# TC264_2024-10-17.net
KiCad netlist of a schematic drawn in EasyEDA Pro
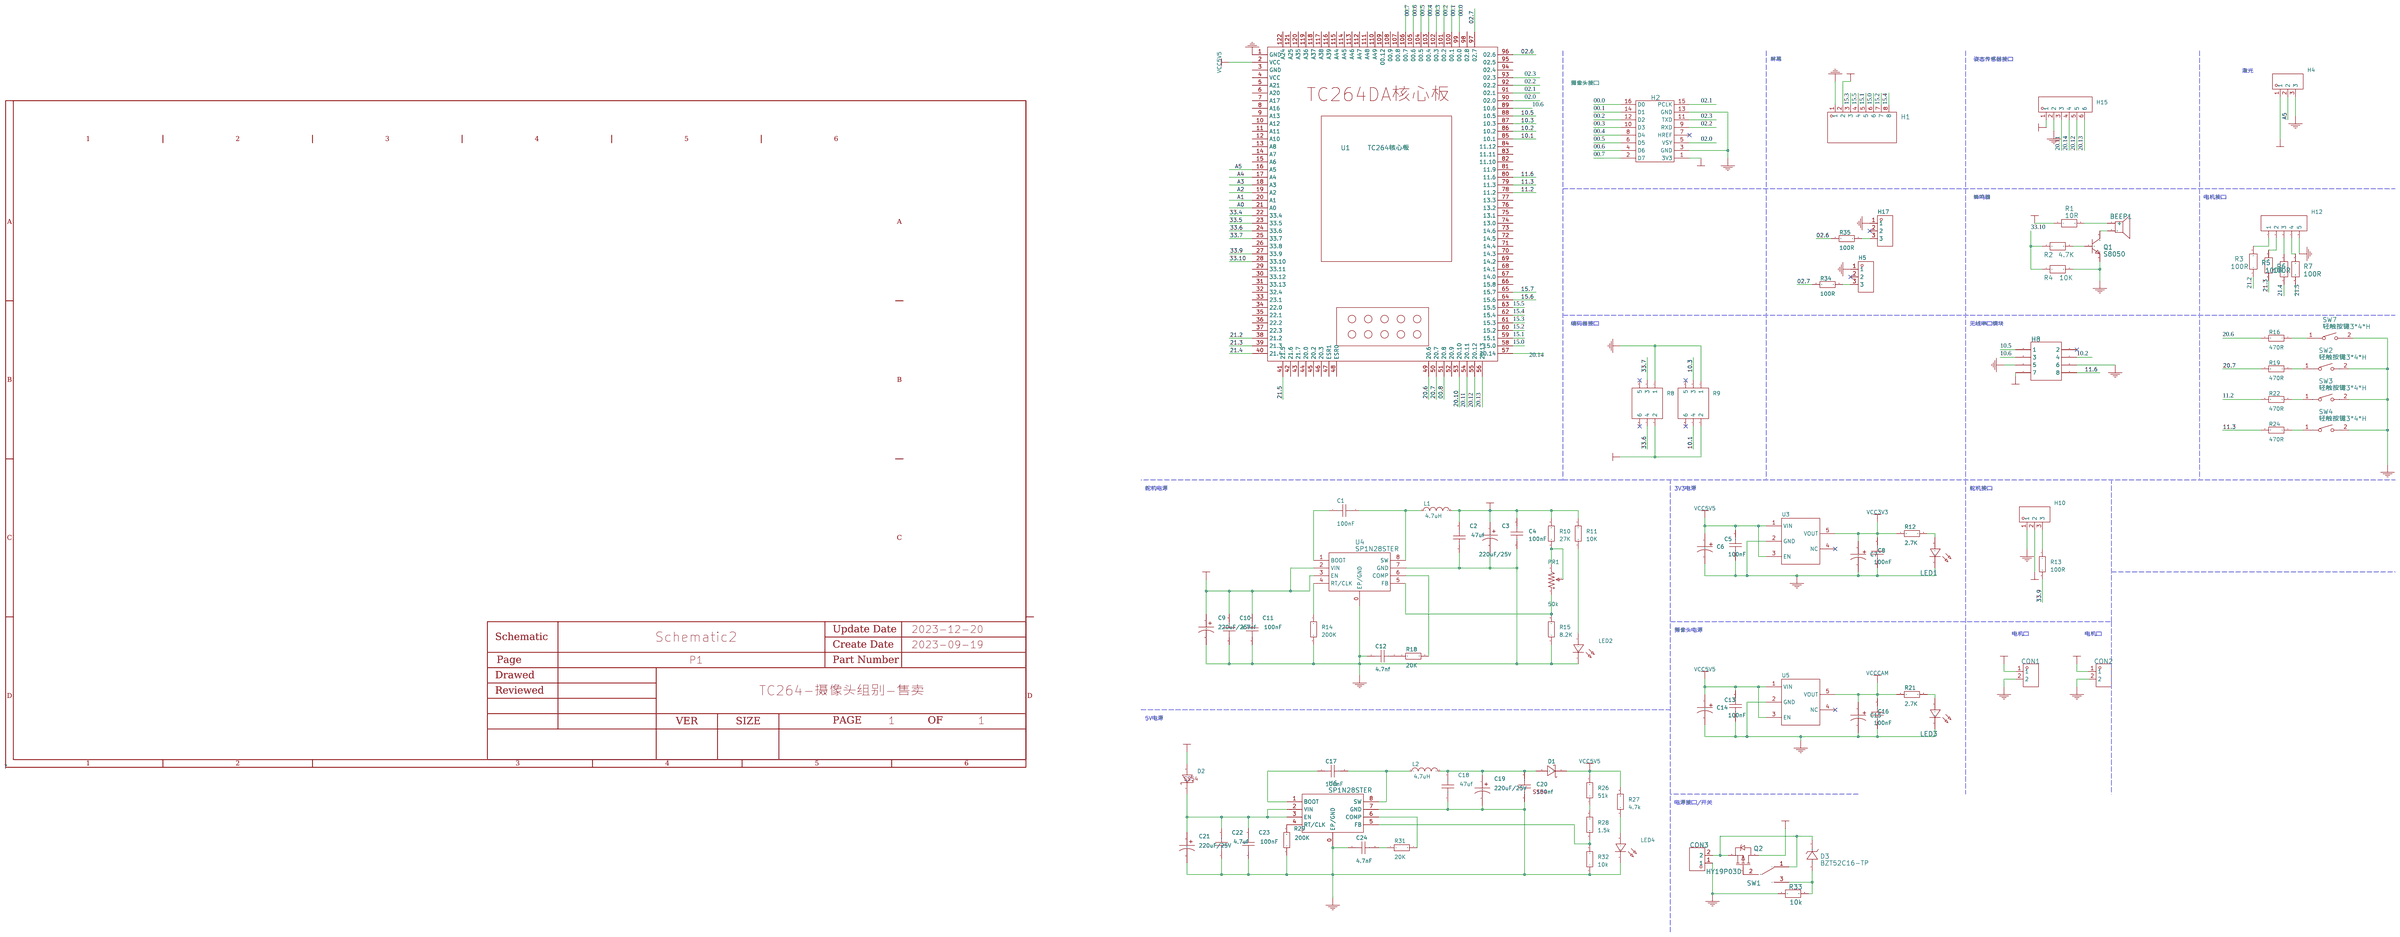
[diagram p0: schematic sheet]

(export (version "E")
  (design (tool "Eeschema 10.0.6"))
  (components
    (comp (ref "BEEP1")
      (value "BEEP-9*5.5")
      (footprint "easyedapro:BEEP-9*5.5")
      (fields (field (name "Manufacturer Part") "HMB1275-05B") (field (name "Manufacturer") "HNDZ"))
      (libsource (lib "easyedapro") (part "BEEP-9*5.5"))
    )
    (comp (ref "C1")
      (value "100nF")
      (footprint "easyedapro:C0603")
      (description "容值:100nF;精度:±10%;额定电压:50V;温度系数:X7R;")
      (libsource (lib "easyedapro") (part "C1210X7R475K630NT"))
    )
    (comp (ref "C2")
      (value "47uf")
      (footprint "easyedapro:C0603")
      (description "容值:100nF;精度:±10%;额定电压:50V;温度系数:X7R;")
      (libsource (lib "easyedapro") (part "C1210X7R475K630NT"))
    )
    (comp (ref "C3")
      (value "220uF/25V")
      (footprint "easyedapro:CAP-TH_BD6.3-P2.50-D1.0-FD")
      (fields
        (field (name "Manufacturer Part") "SHW1000UF6.3V6.3X11")
        (field (name "Manufacturer") "KNSCHA(科尼盛)")
      )
      (libsource (lib "easyedapro") (part "SHW1000UF6.3V6.3X11"))
    )
    (comp (ref "C4")
      (value "100nF")
      (footprint "easyedapro:C0603")
      (description "容值:100nF;精度:±10%;额定电压:50V;温度系数:X7R;")
      (libsource (lib "easyedapro") (part "C1210X7R475K630NT"))
    )
    (comp (ref "C5")
      (value "100nF")
      (footprint "easyedapro:C0603")
      (description "容值:100nF;精度:±10%;额定电压:50V;温度系数:X7R;")
      (libsource (lib "easyedapro") (part "C1210X7R475K630NT"))
    )
    (comp (ref "C6")
      (value "F931A106MAA")
      (footprint "easyedapro:CAP-SMD_L3.2-W1.6-FD")
      (fields (field (name "Manufacturer") "Kyocera AVX"))
      (libsource (lib "easyedapro") (part "F931A106MAA"))
    )
    (comp (ref "C7")
      (value "F931A106MAA")
      (footprint "easyedapro:CAP-SMD_L3.2-W1.6-FD")
      (fields (field (name "Manufacturer") "Kyocera AVX"))
      (libsource (lib "easyedapro") (part "F931A106MAA"))
    )
    (comp (ref "C8")
      (value "100nF")
      (footprint "easyedapro:C0603")
      (description "容值:100nF;精度:±10%;额定电压:50V;温度系数:X7R;")
      (libsource (lib "easyedapro") (part "C1210X7R475K630NT"))
    )
    (comp (ref "C9")
      (value "220uF/25V")
      (footprint "easyedapro:CAP-TH_BD6.3-P2.50-D1.0-FD")
      (fields
        (field (name "Manufacturer Part") "SHW1000UF6.3V6.3X11")
        (field (name "Manufacturer") "KNSCHA(科尼盛)")
      )
      (libsource (lib "easyedapro") (part "SHW1000UF6.3V6.3X11"))
    )
    (comp (ref "C10")
      (value "4.7uf")
      (footprint "easyedapro:C0603")
      (description "容值:100nF;精度:±10%;额定电压:50V;温度系数:X7R;")
      (libsource (lib "easyedapro") (part "C1210X7R475K630NT"))
    )
    (comp (ref "C11")
      (value "100nF")
      (footprint "easyedapro:C0603")
      (description "容值:100nF;精度:±10%;额定电压:50V;温度系数:X7R;")
      (libsource (lib "easyedapro") (part "C1210X7R475K630NT"))
    )
    (comp (ref "C12")
      (value "4.7nf")
      (footprint "easyedapro:C0603")
      (description "容值:100nF;精度:±10%;额定电压:50V;温度系数:X7R;")
      (libsource (lib "easyedapro") (part "C1210X7R475K630NT"))
    )
    (comp (ref "C13")
      (value "100nF")
      (footprint "easyedapro:C0603")
      (description "容值:100nF;精度:±10%;额定电压:50V;温度系数:X7R;")
      (libsource (lib "easyedapro") (part "C1210X7R475K630NT"))
    )
    (comp (ref "C14")
      (value "F931A106MAA")
      (footprint "easyedapro:CAP-SMD_L3.2-W1.6-FD")
      (fields (field (name "Manufacturer") "Kyocera AVX"))
      (libsource (lib "easyedapro") (part "F931A106MAA"))
    )
    (comp (ref "C15")
      (value "F931A106MAA")
      (footprint "easyedapro:CAP-SMD_L3.2-W1.6-FD")
      (fields (field (name "Manufacturer") "Kyocera AVX"))
      (libsource (lib "easyedapro") (part "F931A106MAA"))
    )
    (comp (ref "C16")
      (value "100nF")
      (footprint "easyedapro:C0603")
      (description "容值:100nF;精度:±10%;额定电压:50V;温度系数:X7R;")
      (libsource (lib "easyedapro") (part "C1210X7R475K630NT"))
    )
    (comp (ref "C17")
      (value "100nF")
      (footprint "easyedapro:C0603")
      (description "容值:100nF;精度:±10%;额定电压:50V;温度系数:X7R;")
      (libsource (lib "easyedapro") (part "C1210X7R475K630NT"))
    )
    (comp (ref "C18")
      (value "47uf")
      (footprint "easyedapro:C0603")
      (description "容值:100nF;精度:±10%;额定电压:50V;温度系数:X7R;")
      (libsource (lib "easyedapro") (part "C1210X7R475K630NT"))
    )
    (comp (ref "C19")
      (value "220uF/25V")
      (footprint "easyedapro:CAP-TH_BD6.3-P2.50-D1.0-FD")
      (fields
        (field (name "Manufacturer Part") "SHW1000UF6.3V6.3X11")
        (field (name "Manufacturer") "KNSCHA(科尼盛)")
      )
      (libsource (lib "easyedapro") (part "SHW1000UF6.3V6.3X11"))
    )
    (comp (ref "C20")
      (value "100nf")
      (footprint "easyedapro:C0603")
      (description "容值:100nF;精度:±10%;额定电压:50V;温度系数:X7R;")
      (libsource (lib "easyedapro") (part "C1210X7R475K630NT"))
    )
    (comp (ref "C21")
      (value "220uF/25V")
      (footprint "easyedapro:CAP-TH_BD6.3-P2.50-D1.0-FD")
      (fields
        (field (name "Manufacturer Part") "SHW1000UF6.3V6.3X11")
        (field (name "Manufacturer") "KNSCHA(科尼盛)")
      )
      (libsource (lib "easyedapro") (part "SHW1000UF6.3V6.3X11"))
    )
    (comp (ref "C22")
      (value "4.7uf")
      (footprint "easyedapro:C0603")
      (description "容值:100nF;精度:±10%;额定电压:50V;温度系数:X7R;")
      (libsource (lib "easyedapro") (part "C1210X7R475K630NT"))
    )
    (comp (ref "C23")
      (value "100nF")
      (footprint "easyedapro:C0603")
      (description "容值:100nF;精度:±10%;额定电压:50V;温度系数:X7R;")
      (libsource (lib "easyedapro") (part "C1210X7R475K630NT"))
    )
    (comp (ref "C24")
      (value "4.7nF")
      (footprint "easyedapro:C0603")
      (description "容值:100nF;精度:±10%;额定电压:50V;温度系数:X7R;")
      (libsource (lib "easyedapro") (part "C1210X7R475K630NT"))
    )
    (comp (ref "CON1")
      (value "KF301-5.0-2P")
      (footprint "easyedapro:CONN-TH_P5.00_KF301-5.0-2P")
      (fields (field (name "Manufacturer") "KEFA(科发)"))
      (libsource (lib "easyedapro") (part "KF301-5.0-2P"))
    )
    (comp (ref "CON2")
      (value "KF301-5.0-2P")
      (footprint "easyedapro:CONN-TH_P5.00_KF301-5.0-2P")
      (fields (field (name "Manufacturer") "KEFA(科发)"))
      (libsource (lib "easyedapro") (part "KF301-5.0-2P"))
    )
    (comp (ref "CON3")
      (value "KF301-5.0-2P")
      (footprint "easyedapro:CONN-TH_P5.00_KF301-5.0-2P")
      (fields (field (name "Manufacturer") "KEFA(科发)"))
      (libsource (lib "easyedapro") (part "KF301-5.0-2P"))
    )
    (comp (ref "D1")
      (value "~")
      (footprint "easyedapro:SMB_L4.3-W3.6-LS5.4-RD")
      (description "直流反向耐压(Vr):40V;平均整流电流(Io):5A;正向压降(Vf):550mV@5A;")
      (fields (field (name "Manufacturer Part") "SS54") (field (name "Manufacturer") "LGE(鲁光)"))
      (libsource (lib "easyedapro") (part "SS54_C432139"))
    )
    (comp (ref "D2")
      (value "~")
      (footprint "easyedapro:SMB_L4.3-W3.6-LS5.4-RD")
      (description "直流反向耐压(Vr):40V;平均整流电流(Io):5A;正向压降(Vf):550mV@5A;")
      (fields (field (name "Manufacturer Part") "SS54") (field (name "Manufacturer") "LGE(鲁光)"))
      (libsource (lib "easyedapro") (part "SS54_C432139"))
    )
    (comp (ref "D3")
      (value "BZT52C16-TP")
      (footprint "easyedapro:SOD-123_L2.8-W1.8-LS3.7-RD")
      (fields (field (name "Manufacturer") "MCC(美微科)"))
      (libsource (lib "easyedapro") (part "BZT52C16-TP"))
    )
    (comp (ref "H1")
      (value "屏幕接口")
      (footprint "easyedapro:HDR-TH_8P-P2.54-V_A2541HWV-8P")
      (fields (field (name "Manufacturer Part") "A2541HWV-8P") (field (name "Manufacturer") "CJT(长江连接器)"))
      (libsource (lib "easyedapro") (part "屏幕接口"))
    )
    (comp (ref "H2")
      (value "摄像头接口")
      (footprint "easyedapro:HDR-TH_16P-P2.54-V-F-R2-C8-S2.54")
      (fields (field (name "Manufacturer Part") "DS1023-2*8SF11") (field (name "Manufacturer") "CONNFLY"))
      (libsource (lib "easyedapro") (part "摄像头接口"))
    )
    (comp (ref "H4")
      (value "~")
      (footprint "easyedapro:HDR-TH_3P-P2.54-V-M")
      (libsource (lib "easyedapro") (part "PZ254V-11-03P_C2937625"))
    )
    (comp (ref "H5")
      (value "~")
      (footprint "easyedapro:HDR-TH_3P-P2.54-V-M")
      (libsource (lib "easyedapro") (part "PZ254V-11-03P_C2937625"))
    )
    (comp (ref "H8")
      (value "无线串口模块")
      (footprint "easyedapro:HDR-TH_8P-P2.54-V-F-R2-C4-S2.54-1")
      (fields (field (name "Manufacturer Part") "DS1023-2*4SF11") (field (name "Manufacturer") "CONNFLY"))
      (libsource (lib "easyedapro") (part "DS1023-2*4SF11"))
    )
    (comp (ref "H10")
      (value "~")
      (footprint "easyedapro:HDR-TH_3P-P2.54-V-M")
      (libsource (lib "easyedapro") (part "PZ254V-11-03P_C2937625"))
    )
    (comp (ref "H12")
      (value "~")
      (footprint "easyedapro:HDR-TH_5P-P2.54-V-F")
      (libsource (lib "easyedapro") (part "Header-Female-2.54_1x5"))
    )
    (comp (ref "H15")
      (value "~")
      (footprint "easyedapro:HDR-TH_6P-P2.54-V-F")
      (libsource (lib "easyedapro") (part "Header-Female-2.54_1x6"))
    )
    (comp (ref "H17")
      (value "~")
      (footprint "easyedapro:HDR-TH_3P-P2.54-V-M")
      (libsource (lib "easyedapro") (part "PZ254V-11-03P_C2937625"))
    )
    (comp (ref "L1")
      (value "4.7uH")
      (footprint "easyedapro:IND-SMD_L6.8-W6.8_SMMS0630")
      (description "电感值:33uH;精度:±20%;额定电流:2A;直流电阻(DCR):270mΩ;")
      (fields (field (name "Manufacturer Part") "SMMS0630-330M") (field (name "Manufacturer") "SXN(顺翔诺)"))
      (libsource (lib "easyedapro") (part "SMMS0630-330M"))
    )
    (comp (ref "L2")
      (value "4.7uH")
      (footprint "easyedapro:IND-SMD_L6.8-W6.8_SMMS0630")
      (description "电感值:33uH;精度:±20%;额定电流:2A;直流电阻(DCR):270mΩ;")
      (fields (field (name "Manufacturer Part") "SMMS0630-330M") (field (name "Manufacturer") "SXN(顺翔诺)"))
      (libsource (lib "easyedapro") (part "SMMS0630-330M"))
    )
    (comp (ref "LED1")
      (value "~")
      (footprint "easyedapro:LED0805-RD_RED")
      (libsource (lib "easyedapro") (part "LED_R"))
    )
    (comp (ref "LED2")
      (value "~")
      (footprint "easyedapro:LED0805-RD_RED")
      (libsource (lib "easyedapro") (part "LED_G"))
    )
    (comp (ref "LED3")
      (value "~")
      (footprint "easyedapro:LED0805-RD_RED")
      (libsource (lib "easyedapro") (part "LED_R"))
    )
    (comp (ref "LED4")
      (value "~")
      (footprint "easyedapro:LED0805-RD_RED")
      (libsource (lib "easyedapro") (part "LED_G"))
    )
    (comp (ref "PR1")
      (value "50k")
      (footprint "easyedapro:RES-ADJ-TH_3P-L10.0-W10.0-P2.50-L")
      (description "阻值:10kΩ;精度:±10%;温度系数:±250ppm/;")
      (libsource (lib "easyedapro") (part "3296W-1-103"))
    )
    (comp (ref "Q1")
      (value "S8050")
      (footprint "easyedapro:SOT-23-3_L2.9-W1.3-P1.90-LS2.4-BR")
      (fields (field (name "Manufacturer Part") "S8050/J3Y/0.4") (field (name "Manufacturer") "MOT(仁懋)"))
      (libsource (lib "easyedapro") (part "S8050"))
    )
    (comp (ref "Q2")
      (value "HY19P03D")
      (footprint "easyedapro:TO-252-2_L6.6-W6.1-P4.57-LS9.9-TL-CW")
      (fields (field (name "Manufacturer") "HUAYI(华羿微)"))
      (libsource (lib "easyedapro") (part "HY19P03D"))
    )
    (comp (ref "R1") (value "10R") (footprint "easyedapro:R0603") (libsource (lib "easyedapro") (part "10R")))
    (comp (ref "R2")
      (value "4.7K")
      (footprint "easyedapro:R0603")
      (libsource (lib "easyedapro") (part "4.7K"))
    )
    (comp (ref "R3")
      (value "100R")
      (footprint "easyedapro:R0603")
      (libsource (lib "easyedapro") (part "100R"))
    )
    (comp (ref "R4") (value "10K") (footprint "easyedapro:R0603") (libsource (lib "easyedapro") (part "10K")))
    (comp (ref "R5")
      (value "100R")
      (footprint "easyedapro:R0603")
      (libsource (lib "easyedapro") (part "100R"))
    )
    (comp (ref "R6")
      (value "100R")
      (footprint "easyedapro:R0603")
      (libsource (lib "easyedapro") (part "100R"))
    )
    (comp (ref "R7")
      (value "100R")
      (footprint "easyedapro:R0603")
      (libsource (lib "easyedapro") (part "100R"))
    )
    (comp (ref "R8")
      (value "100R")
      (footprint "easyedapro:HDR-TH_6P-P2.54-V-F-R2-C3-S2.54")
      (libsource (lib "easyedapro") (part "HDR-F-2.54_2x3"))
    )
    (comp (ref "R9")
      (value "100R")
      (footprint "easyedapro:HDR-TH_6P-P2.54-V-F-R2-C3-S2.54")
      (libsource (lib "easyedapro") (part "HDR-F-2.54_2x3"))
    )
    (comp (ref "R10") (value "27K") (footprint "easyedapro:R0603") (libsource (lib "easyedapro") (part "电阻")))
    (comp (ref "R11") (value "10K") (footprint "easyedapro:R0603") (libsource (lib "easyedapro") (part "电阻")))
    (comp (ref "R12")
      (value "2.7K")
      (footprint "easyedapro:R0603")
      (libsource (lib "easyedapro") (part "电阻"))
    )
    (comp (ref "R13")
      (value "100R")
      (footprint "easyedapro:R0603")
      (libsource (lib "easyedapro") (part "电阻"))
    )
    (comp (ref "R14")
      (value "200K")
      (footprint "easyedapro:R0603")
      (libsource (lib "easyedapro") (part "电阻"))
    )
    (comp (ref "R15")
      (value "8.2K")
      (footprint "easyedapro:R0603")
      (libsource (lib "easyedapro") (part "电阻"))
    )
    (comp (ref "R16")
      (value "470R")
      (footprint "easyedapro:RES-TH_BD1.8-L3.2-P7.20-D0.4")
      (libsource (lib "easyedapro") (part "电阻"))
    )
    (comp (ref "R18") (value "20K") (footprint "easyedapro:R0603") (libsource (lib "easyedapro") (part "电阻")))
    (comp (ref "R19")
      (value "470R")
      (footprint "easyedapro:RES-TH_BD1.8-L3.2-P7.20-D0.4")
      (libsource (lib "easyedapro") (part "电阻"))
    )
    (comp (ref "R21")
      (value "2.7K")
      (footprint "easyedapro:R0603")
      (libsource (lib "easyedapro") (part "电阻"))
    )
    (comp (ref "R22")
      (value "470R")
      (footprint "easyedapro:RES-TH_BD1.8-L3.2-P7.20-D0.4")
      (libsource (lib "easyedapro") (part "电阻"))
    )
    (comp (ref "R24")
      (value "470R")
      (footprint "easyedapro:RES-TH_BD1.8-L3.2-P7.20-D0.4")
      (libsource (lib "easyedapro") (part "电阻"))
    )
    (comp (ref "R26") (value "51k") (footprint "easyedapro:R0603") (libsource (lib "easyedapro") (part "电阻")))
    (comp (ref "R27")
      (value "4.7k")
      (footprint "easyedapro:R0603")
      (libsource (lib "easyedapro") (part "电阻"))
    )
    (comp (ref "R28")
      (value "1.5k")
      (footprint "easyedapro:R0603")
      (libsource (lib "easyedapro") (part "电阻"))
    )
    (comp (ref "R29")
      (value "200K")
      (footprint "easyedapro:R0603")
      (libsource (lib "easyedapro") (part "电阻"))
    )
    (comp (ref "R31") (value "20K") (footprint "easyedapro:R0603") (libsource (lib "easyedapro") (part "电阻")))
    (comp (ref "R32") (value "10k") (footprint "easyedapro:R0603") (libsource (lib "easyedapro") (part "电阻")))
    (comp (ref "R33") (value "10k") (footprint "easyedapro:R0603") (libsource (lib "easyedapro") (part "1k")))
    (comp (ref "R34")
      (value "100R")
      (footprint "easyedapro:RES-TH_BD1.8-L3.2-P7.20-D0.4")
      (libsource (lib "easyedapro") (part "电阻"))
    )
    (comp (ref "R35")
      (value "100R")
      (footprint "easyedapro:RES-TH_BD1.8-L3.2-P7.20-D0.4")
      (libsource (lib "easyedapro") (part "电阻"))
    )
    (comp (ref "SW1")
      (value "SS12D10")
      (footprint "easyedapro:SS12D10")
      (libsource (lib "easyedapro") (part "SS12D10"))
    )
    (comp (ref "SW2")
      (value "轻触按键3*4*H")
      (footprint "easyedapro:SW-SMD_L4.0-W2.9-LS5.0")
      (libsource (lib "easyedapro") (part "轻触按键3*4*H"))
    )
    (comp (ref "SW3")
      (value "轻触按键3*4*H")
      (footprint "easyedapro:SW-SMD_L4.0-W2.9-LS5.0")
      (libsource (lib "easyedapro") (part "轻触按键3*4*H"))
    )
    (comp (ref "SW4")
      (value "轻触按键3*4*H")
      (footprint "easyedapro:SW-SMD_L4.0-W2.9-LS5.0")
      (libsource (lib "easyedapro") (part "轻触按键3*4*H"))
    )
    (comp (ref "SW7")
      (value "轻触按键3*4*H")
      (footprint "easyedapro:SW-SMD_L4.0-W2.9-LS5.0")
      (libsource (lib "easyedapro") (part "轻触按键3*4*H"))
    )
    (comp (ref "U1")
      (value "TC264核心板")
      (footprint "easyedapro:TC264DA核心板封装")
      (libsource (lib "easyedapro") (part "TC264核心板"))
    )
    (comp (ref "U3")
      (value "RT9013-33GB")
      (footprint "easyedapro:SOT-23-5_L3.0-W1.7-P0.95-LS2.8-BR")
      (fields (field (name "Manufacturer") "RICHTEK(台湾立锜)"))
      (libsource (lib "easyedapro") (part "RT9013-33GB"))
    )
    (comp (ref "U4")
      (value "SP1N28STER")
      (footprint "easyedapro:SOP-8E")
      (libsource (lib "easyedapro") (part "SP1N28STER"))
    )
    (comp (ref "U5")
      (value "RT9013-33GB")
      (footprint "easyedapro:SOT-23-5_L3.0-W1.7-P0.95-LS2.8-BR")
      (fields (field (name "Manufacturer") "RICHTEK(台湾立锜)"))
      (libsource (lib "easyedapro") (part "RT9013-33GB"))
    )
    (comp (ref "U6")
      (value "SP1N28STER")
      (footprint "easyedapro:SOP-8E")
      (libsource (lib "easyedapro") (part "SP1N28STER"))
    )
  )
  (nets
    (net (code "1") (name "/00.0") (class "Default")
      (node (ref "H2") (pin "16") (pinfunction "D0_16") (pintype "input"))
      (node (ref "U1") (pin "99") (pinfunction "00.0_99") (pintype "input"))
    )
    (net (code "2") (name "/00.1") (class "Default")
      (node (ref "H2") (pin "14") (pinfunction "D1_14") (pintype "input"))
      (node (ref "U1") (pin "100") (pinfunction "00.1_100") (pintype "input"))
    )
    (net (code "3") (name "/00.2") (class "Default")
      (node (ref "H2") (pin "12") (pinfunction "D2_12") (pintype "input"))
      (node (ref "U1") (pin "101") (pinfunction "00.2_101") (pintype "input"))
    )
    (net (code "4") (name "/00.3") (class "Default")
      (node (ref "H2") (pin "10") (pinfunction "D3_10") (pintype "input"))
      (node (ref "U1") (pin "102") (pinfunction "00.3_102") (pintype "input"))
    )
    (net (code "5") (name "/00.4") (class "Default")
      (node (ref "H2") (pin "8") (pinfunction "D4_8") (pintype "input"))
      (node (ref "U1") (pin "103") (pinfunction "00.4_103") (pintype "input"))
    )
    (net (code "6") (name "/00.5") (class "Default")
      (node (ref "H2") (pin "6") (pinfunction "D5_6") (pintype "input"))
      (node (ref "U1") (pin "104") (pinfunction "00.5_104") (pintype "input"))
    )
    (net (code "7") (name "/00.6") (class "Default")
      (node (ref "H2") (pin "4") (pinfunction "D6_4") (pintype "input"))
      (node (ref "U1") (pin "105") (pinfunction "00.6_105") (pintype "input"))
    )
    (net (code "8") (name "/00.7") (class "Default")
      (node (ref "H2") (pin "2") (pinfunction "D7_2") (pintype "input"))
      (node (ref "U1") (pin "106") (pinfunction "00.7_106") (pintype "input"))
    )
    (net (code "9") (name "/00.8") (class "Default")
      (node (ref "U1") (pin "51") (pinfunction "20.8_51") (pintype "input"))
    )
    (net (code "10") (name "/02.0") (class "Default")
      (node (ref "H2") (pin "5") (pinfunction "VSY_5") (pintype "input"))
      (node (ref "U1") (pin "90") (pinfunction "02.0_90") (pintype "input"))
    )
    (net (code "11") (name "/02.1") (class "Default")
      (node (ref "H2") (pin "15") (pinfunction "PCLK_15") (pintype "input"))
      (node (ref "U1") (pin "91") (pinfunction "02.1_91") (pintype "input"))
    )
    (net (code "12") (name "/02.2") (class "Default")
      (node (ref "H2") (pin "9") (pinfunction "RXD_9") (pintype "input"))
      (node (ref "U1") (pin "92") (pinfunction "02.2_92") (pintype "input"))
    )
    (net (code "13") (name "/02.3") (class "Default")
      (node (ref "H2") (pin "11") (pinfunction "TXD_11") (pintype "input"))
      (node (ref "U1") (pin "93") (pinfunction "02.3_93") (pintype "input"))
    )
    (net (code "14") (name "/02.6") (class "Default")
      (node (ref "R35") (pin "2") (pinfunction "2_2") (pintype "input"))
      (node (ref "U1") (pin "96") (pinfunction "02.6_96") (pintype "input"))
    )
    (net (code "15") (name "/02.7") (class "Default")
      (node (ref "R34") (pin "2") (pinfunction "2_2") (pintype "input"))
      (node (ref "U1") (pin "97") (pinfunction "02.7_97") (pintype "input"))
    )
    (net (code "16") (name "/10.1") (class "Default")
      (node (ref "R9") (pin "4") (pinfunction "4_4") (pintype "input"))
      (node (ref "U1") (pin "85") (pinfunction "10.1_85") (pintype "input"))
    )
    (net (code "17") (name "/10.2") (class "Default")
      (node (ref "H8") (pin "4") (pinfunction "4_4") (pintype "input"))
      (node (ref "U1") (pin "86") (pinfunction "10.2_86") (pintype "input"))
    )
    (net (code "18") (name "/10.3") (class "Default")
      (node (ref "R9") (pin "3") (pinfunction "3_3") (pintype "input"))
      (node (ref "U1") (pin "87") (pinfunction "10.3_87") (pintype "input"))
    )
    (net (code "19") (name "/10.5") (class "Default")
      (node (ref "H8") (pin "1") (pinfunction "1_1") (pintype "input"))
      (node (ref "U1") (pin "88") (pinfunction "10.5_88") (pintype "input"))
    )
    (net (code "20") (name "/10.6") (class "Default")
      (node (ref "H8") (pin "3") (pinfunction "3_3") (pintype "input"))
      (node (ref "U1") (pin "89") (pinfunction "10.6_89") (pintype "input"))
    )
    (net (code "21") (name "/11.2") (class "Default")
      (node (ref "R22") (pin "2") (pinfunction "2_2") (pintype "input"))
      (node (ref "U1") (pin "78") (pinfunction "11.2_78") (pintype "input"))
    )
    (net (code "22") (name "/11.3") (class "Default")
      (node (ref "R24") (pin "2") (pinfunction "2_2") (pintype "input"))
      (node (ref "U1") (pin "79") (pinfunction "11.3_79") (pintype "input"))
    )
    (net (code "23") (name "/11.6") (class "Default")
      (node (ref "H8") (pin "8") (pinfunction "8_8") (pintype "input"))
      (node (ref "U1") (pin "80") (pinfunction "11.6_80") (pintype "input"))
    )
    (net (code "24") (name "/15.0") (class "Default")
      (node (ref "H1") (pin "6") (pinfunction "6_6") (pintype "input"))
      (node (ref "U1") (pin "58") (pinfunction "15.0_58") (pintype "input"))
    )
    (net (code "25") (name "/15.1") (class "Default")
      (node (ref "H1") (pin "5") (pinfunction "5_5") (pintype "input"))
      (node (ref "U1") (pin "59") (pinfunction "15.1_59") (pintype "input"))
    )
    (net (code "26") (name "/15.2") (class "Default")
      (node (ref "H1") (pin "7") (pinfunction "7_7") (pintype "input"))
      (node (ref "U1") (pin "60") (pinfunction "15.2_60") (pintype "input"))
    )
    (net (code "27") (name "/15.3") (class "Default")
      (node (ref "H1") (pin "3") (pinfunction "3_3") (pintype "input"))
      (node (ref "U1") (pin "61") (pinfunction "15.3_61") (pintype "input"))
    )
    (net (code "28") (name "/15.4") (class "Default")
      (node (ref "H1") (pin "8") (pinfunction "8_8") (pintype "input"))
      (node (ref "U1") (pin "62") (pinfunction "15.4_62") (pintype "input"))
    )
    (net (code "29") (name "/15.5") (class "Default")
      (node (ref "H1") (pin "4") (pinfunction "4_4") (pintype "input"))
      (node (ref "U1") (pin "63") (pinfunction "15.5_63") (pintype "input"))
    )
    (net (code "30") (name "/15.6") (class "Default")
      (node (ref "U1") (pin "64") (pinfunction "15.6_64") (pintype "input"))
    )
    (net (code "31") (name "/15.7") (class "Default")
      (node (ref "U1") (pin "65") (pinfunction "15.7_65") (pintype "input"))
    )
    (net (code "32") (name "/20.6") (class "Default")
      (node (ref "R16") (pin "2") (pinfunction "2_2") (pintype "input"))
      (node (ref "U1") (pin "49") (pinfunction "20.6_49") (pintype "input"))
    )
    (net (code "33") (name "/20.7") (class "Default")
      (node (ref "R19") (pin "2") (pinfunction "2_2") (pintype "input"))
      (node (ref "U1") (pin "50") (pinfunction "20.7_50") (pintype "input"))
    )
    (net (code "34") (name "/20.10") (class "Default")
      (node (ref "U1") (pin "53") (pinfunction "20.10_53") (pintype "input"))
    )
    (net (code "35") (name "/20.11") (class "Default")
      (node (ref "H15") (pin "3") (pinfunction "3_3") (pintype "unspecified"))
      (node (ref "U1") (pin "54") (pinfunction "20.11_54") (pintype "input"))
    )
    (net (code "36") (name "/20.12") (class "Default")
      (node (ref "H15") (pin "5") (pinfunction "5_5") (pintype "unspecified"))
      (node (ref "U1") (pin "55") (pinfunction "20.12_55") (pintype "input"))
    )
    (net (code "37") (name "/20.13") (class "Default")
      (node (ref "H15") (pin "6") (pinfunction "6_6") (pintype "unspecified"))
      (node (ref "U1") (pin "56") (pinfunction "20.13_56") (pintype "input"))
    )
    (net (code "38") (name "/20.14") (class "Default")
      (node (ref "H15") (pin "4") (pinfunction "4_4") (pintype "unspecified"))
      (node (ref "U1") (pin "57") (pinfunction "20.14_57") (pintype "input"))
    )
    (net (code "39") (name "/21.2") (class "Default")
      (node (ref "R3") (pin "1") (pinfunction "1_1") (pintype "input"))
      (node (ref "U1") (pin "38") (pinfunction "21.2_38") (pintype "input"))
    )
    (net (code "40") (name "/21.3") (class "Default")
      (node (ref "R5") (pin "2") (pinfunction "2_2") (pintype "input"))
      (node (ref "U1") (pin "39") (pinfunction "21.3_39") (pintype "input"))
    )
    (net (code "41") (name "/21.4") (class "Default")
      (node (ref "R6") (pin "1") (pinfunction "1_1") (pintype "input"))
      (node (ref "U1") (pin "40") (pinfunction "21.4_40") (pintype "input"))
    )
    (net (code "42") (name "/21.5") (class "Default")
      (node (ref "R7") (pin "2") (pinfunction "2_2") (pintype "input"))
      (node (ref "U1") (pin "41") (pinfunction "21.5_41") (pintype "input"))
    )
    (net (code "43") (name "/33.4") (class "Default")
      (node (ref "U1") (pin "22") (pinfunction "33.4_22") (pintype "input"))
    )
    (net (code "44") (name "/33.5") (class "Default")
      (node (ref "U1") (pin "23") (pinfunction "33.5_23") (pintype "input"))
    )
    (net (code "45") (name "/33.6") (class "Default")
      (node (ref "R8") (pin "4") (pinfunction "4_4") (pintype "input"))
      (node (ref "U1") (pin "24") (pinfunction "33.6_24") (pintype "input"))
    )
    (net (code "46") (name "/33.7") (class "Default")
      (node (ref "R8") (pin "3") (pinfunction "3_3") (pintype "input"))
      (node (ref "U1") (pin "25") (pinfunction "33.7_25") (pintype "input"))
    )
    (net (code "47") (name "/33.9") (class "Default")
      (node (ref "R13") (pin "2") (pinfunction "2_2") (pintype "input"))
      (node (ref "U1") (pin "27") (pinfunction "33.9_27") (pintype "input"))
    )
    (net (code "48") (name "/33.10") (class "Default")
      (node (ref "R2") (pin "1") (pinfunction "1_1") (pintype "input"))
      (node (ref "R4") (pin "1") (pinfunction "1_1") (pintype "input"))
      (node (ref "U1") (pin "28") (pinfunction "33.10_28") (pintype "input"))
    )
    (net (code "49") (name "/A0") (class "Default")
      (node (ref "U1") (pin "21") (pinfunction "A0_21") (pintype "input"))
    )
    (net (code "50") (name "/A1") (class "Default")
      (node (ref "U1") (pin "20") (pinfunction "A1_20") (pintype "input"))
    )
    (net (code "51") (name "/A2") (class "Default")
      (node (ref "U1") (pin "19") (pinfunction "A2_19") (pintype "input"))
    )
    (net (code "52") (name "/A3") (class "Default")
      (node (ref "U1") (pin "18") (pinfunction "A3_18") (pintype "input"))
    )
    (net (code "53") (name "/A4") (class "Default")
      (node (ref "U1") (pin "17") (pinfunction "A4_17") (pintype "input"))
    )
    (net (code "54") (name "/A5") (class "Default")
      (node (ref "H4") (pin "2") (pinfunction "2_2") (pintype "input"))
      (node (ref "U1") (pin "16") (pinfunction "A5_16") (pintype "input"))
    )
    (net (code "55") (name "GNDBAT") (class "Default")
      (node (ref "C10") (pin "1") (pinfunction "1_1") (pintype "input"))
      (node (ref "C11") (pin "1") (pinfunction "1_1") (pintype "input"))
      (node (ref "C12") (pin "1") (pinfunction "1_1") (pintype "input"))
      (node (ref "C13") (pin "1") (pinfunction "1_1") (pintype "input"))
      (node (ref "C14") (pin "2") (pinfunction "2_2") (pintype "input"))
      (node (ref "C15") (pin "2") (pinfunction "2_2") (pintype "input"))
      (node (ref "C16") (pin "1") (pinfunction "1_1") (pintype "input"))
      (node (ref "C18") (pin "1") (pinfunction "1_1") (pintype "input"))
      (node (ref "C19") (pin "2") (pinfunction "2_2") (pintype "input"))
      (node (ref "C2") (pin "1") (pinfunction "1_1") (pintype "input"))
      (node (ref "C20") (pin "1") (pinfunction "1_1") (pintype "input"))
      (node (ref "C21") (pin "2") (pinfunction "2_2") (pintype "input"))
      (node (ref "C22") (pin "1") (pinfunction "1_1") (pintype "input"))
      (node (ref "C23") (pin "1") (pinfunction "1_1") (pintype "input"))
      (node (ref "C24") (pin "1") (pinfunction "1_1") (pintype "input"))
      (node (ref "C3") (pin "2") (pinfunction "2_2") (pintype "input"))
      (node (ref "C4") (pin "1") (pinfunction "1_1") (pintype "input"))
      (node (ref "C5") (pin "1") (pinfunction "1_1") (pintype "input"))
      (node (ref "C6") (pin "2") (pinfunction "2_2") (pintype "input"))
      (node (ref "C7") (pin "2") (pinfunction "2_2") (pintype "input"))
      (node (ref "C8") (pin "1") (pinfunction "1_1") (pintype "input"))
      (node (ref "C9") (pin "2") (pinfunction "2_2") (pintype "input"))
      (node (ref "CON1") (pin "2") (pinfunction "2_2") (pintype "input"))
      (node (ref "CON2") (pin "2") (pinfunction "2_2") (pintype "input"))
      (node (ref "CON3") (pin "1") (pinfunction "1_1") (pintype "input"))
      (node (ref "H1") (pin "1") (pinfunction "1_1") (pintype "input"))
      (node (ref "H10") (pin "1") (pinfunction "1_1") (pintype "input"))
      (node (ref "H12") (pin "5") (pinfunction "5_5") (pintype "input"))
      (node (ref "H15") (pin "2") (pinfunction "2_2") (pintype "unspecified"))
      (node (ref "H17") (pin "1") (pinfunction "1_1") (pintype "input"))
      (node (ref "H2") (pin "13") (pinfunction "GND_13") (pintype "input"))
      (node (ref "H2") (pin "3") (pinfunction "GND_3") (pintype "input"))
      (node (ref "H4") (pin "3") (pinfunction "3_3") (pintype "input"))
      (node (ref "H5") (pin "1") (pinfunction "1_1") (pintype "input"))
      (node (ref "H8") (pin "5") (pinfunction "5_5") (pintype "input"))
      (node (ref "H8") (pin "6") (pinfunction "6_6") (pintype "input"))
      (node (ref "LED1") (pin "1") (pinfunction "C_1") (pintype "input"))
      (node (ref "LED2") (pin "1") (pinfunction "C_1") (pintype "input"))
      (node (ref "LED3") (pin "1") (pinfunction "C_1") (pintype "input"))
      (node (ref "LED4") (pin "1") (pinfunction "C_1") (pintype "input"))
      (node (ref "Q1") (pin "2") (pinfunction "E_2") (pintype "input"))
      (node (ref "R14") (pin "2") (pinfunction "2_2") (pintype "input"))
      (node (ref "R15") (pin "1") (pinfunction "1_1") (pintype "input"))
      (node (ref "R29") (pin "1") (pinfunction "1_1") (pintype "input"))
      (node (ref "R32") (pin "1") (pinfunction "1_1") (pintype "input"))
      (node (ref "R33") (pin "1") (pinfunction "1_1") (pintype "input"))
      (node (ref "R4") (pin "2") (pinfunction "2_2") (pintype "input"))
      (node (ref "R8") (pin "1") (pinfunction "1_1") (pintype "input"))
      (node (ref "R9") (pin "1") (pinfunction "1_1") (pintype "input"))
      (node (ref "SW2") (pin "2") (pinfunction "2_2") (pintype "input"))
      (node (ref "SW3") (pin "2") (pinfunction "2_2") (pintype "input"))
      (node (ref "SW4") (pin "2") (pinfunction "2_2") (pintype "input"))
      (node (ref "SW7") (pin "2") (pinfunction "2_2") (pintype "input"))
      (node (ref "U1") (pin "1") (pinfunction "GND_1") (pintype "input"))
      (node (ref "U3") (pin "2") (pinfunction "GND_2") (pintype "input"))
      (node (ref "U4") (pin "0") (pinfunction "EP/GND_0") (pintype "input"))
      (node (ref "U4") (pin "7") (pinfunction "GND_7") (pintype "input"))
      (node (ref "U5") (pin "2") (pinfunction "GND_2") (pintype "input"))
      (node (ref "U6") (pin "0") (pinfunction "EP/GND_0") (pintype "input"))
      (node (ref "U6") (pin "7") (pinfunction "GND_7") (pintype "input"))
    )
    (net (code "56") (name "Net-(BEEP1-+)") (class "Default")
      (node (ref "BEEP1") (pin "1") (pinfunction "+_1") (pintype "input"))
      (node (ref "R1") (pin "2") (pinfunction "2_2") (pintype "input"))
    )
    (net (code "57") (name "Net-(C12-Pad2)") (class "Default")
      (node (ref "C12") (pin "2") (pinfunction "2_2") (pintype "input"))
      (node (ref "R18") (pin "1") (pinfunction "1_1") (pintype "input"))
    )
    (net (code "58") (name "Net-(C24-Pad2)") (class "Default")
      (node (ref "C24") (pin "2") (pinfunction "2_2") (pintype "input"))
      (node (ref "R31") (pin "1") (pinfunction "1_1") (pintype "input"))
    )
    (net (code "59") (name "Net-(D1-A)") (class "Default")
      (node (ref "C18") (pin "2") (pinfunction "2_2") (pintype "input"))
      (node (ref "C19") (pin "1") (pinfunction "1_1") (pintype "input"))
      (node (ref "C20") (pin "2") (pinfunction "2_2") (pintype "input"))
      (node (ref "D1") (pin "2") (pinfunction "A_2") (pintype "input"))
      (node (ref "L2") (pin "2") (pinfunction "2_2") (pintype "input"))
    )
    (net (code "60") (name "Net-(D2-C)") (class "Default")
      (node (ref "C21") (pin "1") (pinfunction "1_1") (pintype "input"))
      (node (ref "C22") (pin "2") (pinfunction "2_2") (pintype "input"))
      (node (ref "C23") (pin "2") (pinfunction "2_2") (pintype "input"))
      (node (ref "D2") (pin "1") (pinfunction "C_1") (pintype "input"))
      (node (ref "U6") (pin "2") (pinfunction "VIN_2") (pintype "input"))
      (node (ref "U6") (pin "3") (pinfunction "EN_3") (pintype "input"))
    )
    (net (code "61") (name "Net-(D3-A)") (class "Default")
      (node (ref "D3") (pin "2") (pinfunction "A_2") (pintype "input"))
      (node (ref "R33") (pin "2") (pinfunction "2_2") (pintype "input"))
      (node (ref "SW1") (pin "3") (pinfunction "3_3") (pintype "input"))
    )
    (net (code "62") (name "Net-(D3-C)") (class "Default")
      (node (ref "CON3") (pin "2") (pinfunction "2_2") (pintype "input"))
      (node (ref "D3") (pin "1") (pinfunction "C_1") (pintype "input"))
      (node (ref "Q2") (pin "3") (pinfunction "S_3") (pintype "input"))
      (node (ref "SW1") (pin "1") (pinfunction "1_1") (pintype "input"))
    )
    (net (code "63") (name "Net-(H5-Pad3)") (class "Default")
      (node (ref "H5") (pin "3") (pinfunction "3_3") (pintype "input"))
      (node (ref "R34") (pin "1") (pinfunction "1_1") (pintype "input"))
    )
    (net (code "64") (name "Net-(H10-Pad3)") (class "Default")
      (node (ref "H10") (pin "3") (pinfunction "3_3") (pintype "input"))
      (node (ref "R13") (pin "1") (pinfunction "1_1") (pintype "input"))
    )
    (net (code "65") (name "Net-(H12-Pad1)") (class "Default")
      (node (ref "H12") (pin "1") (pinfunction "1_1") (pintype "input"))
      (node (ref "R3") (pin "2") (pinfunction "2_2") (pintype "input"))
    )
    (net (code "66") (name "Net-(H12-Pad2)") (class "Default")
      (node (ref "H12") (pin "2") (pinfunction "2_2") (pintype "input"))
      (node (ref "R5") (pin "1") (pinfunction "1_1") (pintype "input"))
    )
    (net (code "67") (name "Net-(H12-Pad3)") (class "Default")
      (node (ref "H12") (pin "3") (pinfunction "3_3") (pintype "input"))
      (node (ref "R6") (pin "2") (pinfunction "2_2") (pintype "input"))
    )
    (net (code "68") (name "Net-(H12-Pad4)") (class "Default")
      (node (ref "H12") (pin "4") (pinfunction "4_4") (pintype "input"))
      (node (ref "R7") (pin "1") (pinfunction "1_1") (pintype "input"))
    )
    (net (code "69") (name "Net-(H17-Pad3)") (class "Default")
      (node (ref "H17") (pin "3") (pinfunction "3_3") (pintype "input"))
      (node (ref "R35") (pin "1") (pinfunction "1_1") (pintype "input"))
    )
    (net (code "70") (name "Net-(LED1-A)") (class "Default")
      (node (ref "LED1") (pin "2") (pinfunction "A_2") (pintype "input"))
      (node (ref "R12") (pin "2") (pinfunction "2_2") (pintype "input"))
    )
    (net (code "71") (name "Net-(LED2-A)") (class "Default")
      (node (ref "LED2") (pin "2") (pinfunction "A_2") (pintype "input"))
      (node (ref "R11") (pin "1") (pinfunction "1_1") (pintype "input"))
    )
    (net (code "72") (name "Net-(LED3-A)") (class "Default")
      (node (ref "LED3") (pin "2") (pinfunction "A_2") (pintype "input"))
      (node (ref "R21") (pin "2") (pinfunction "2_2") (pintype "input"))
    )
    (net (code "73") (name "Net-(LED4-A)") (class "Default")
      (node (ref "LED4") (pin "2") (pinfunction "A_2") (pintype "input"))
      (node (ref "R27") (pin "1") (pinfunction "1_1") (pintype "input"))
    )
    (net (code "74") (name "Net-(PR1-Pad2)") (class "Default")
      (node (ref "PR1") (pin "2") (pinfunction "2_2") (pintype "input"))
      (node (ref "PR1") (pin "3") (pinfunction "3_3") (pintype "input"))
      (node (ref "R10") (pin "1") (pinfunction "1_1") (pintype "input"))
    )
    (net (code "75") (name "Net-(Q1-B)") (class "Default")
      (node (ref "Q1") (pin "1") (pinfunction "B_1") (pintype "input"))
      (node (ref "R2") (pin "2") (pinfunction "2_2") (pintype "input"))
    )
    (net (code "76") (name "Net-(Q1-C)") (class "Default")
      (node (ref "BEEP1") (pin "2") (pinfunction "2_2") (pintype "input"))
      (node (ref "Q1") (pin "3") (pinfunction "C_3") (pintype "input"))
    )
    (net (code "77") (name "Net-(Q2-G)") (class "Default")
      (node (ref "Q2") (pin "1") (pinfunction "G_1") (pintype "input"))
      (node (ref "SW1") (pin "2") (pinfunction "2_2") (pintype "input"))
    )
    (net (code "78") (name "Net-(R16-Pad1)") (class "Default")
      (node (ref "R16") (pin "1") (pinfunction "1_1") (pintype "input"))
      (node (ref "SW7") (pin "1") (pinfunction "1_1") (pintype "input"))
    )
    (net (code "79") (name "Net-(R19-Pad1)") (class "Default")
      (node (ref "R19") (pin "1") (pinfunction "1_1") (pintype "input"))
      (node (ref "SW2") (pin "1") (pinfunction "1_1") (pintype "input"))
    )
    (net (code "80") (name "Net-(R22-Pad1)") (class "Default")
      (node (ref "R22") (pin "1") (pinfunction "1_1") (pintype "input"))
      (node (ref "SW3") (pin "1") (pinfunction "1_1") (pintype "input"))
    )
    (net (code "81") (name "Net-(R24-Pad1)") (class "Default")
      (node (ref "R24") (pin "1") (pinfunction "1_1") (pintype "input"))
      (node (ref "SW4") (pin "1") (pinfunction "1_1") (pintype "input"))
    )
    (net (code "82") (name "Net-(R26-Pad1)") (class "Default")
      (node (ref "R26") (pin "1") (pinfunction "1_1") (pintype "input"))
      (node (ref "R28") (pin "2") (pinfunction "2_2") (pintype "input"))
    )
    (net (code "83") (name "Net-(U4-BOOT)") (class "Default")
      (node (ref "C1") (pin "1") (pinfunction "1_1") (pintype "input"))
      (node (ref "U4") (pin "1") (pinfunction "BOOT_1") (pintype "input"))
    )
    (net (code "84") (name "Net-(U4-COMP)") (class "Default")
      (node (ref "R18") (pin "2") (pinfunction "2_2") (pintype "input"))
      (node (ref "U4") (pin "6") (pinfunction "COMP_6") (pintype "input"))
    )
    (net (code "85") (name "Net-(U4-FB)") (class "Default")
      (node (ref "PR1") (pin "1") (pinfunction "1_1") (pintype "input"))
      (node (ref "R15") (pin "2") (pinfunction "2_2") (pintype "input"))
      (node (ref "U4") (pin "5") (pinfunction "FB_5") (pintype "input"))
    )
    (net (code "86") (name "Net-(U4-RT{slash}CLK)") (class "Default")
      (node (ref "R14") (pin "1") (pinfunction "1_1") (pintype "input"))
      (node (ref "U4") (pin "4") (pinfunction "RT/CLK_4") (pintype "input"))
    )
    (net (code "87") (name "Net-(U4-SW)") (class "Default")
      (node (ref "C1") (pin "2") (pinfunction "2_2") (pintype "input"))
      (node (ref "L1") (pin "1") (pinfunction "1_1") (pintype "input"))
      (node (ref "U4") (pin "8") (pinfunction "SW_8") (pintype "input"))
    )
    (net (code "88") (name "Net-(U6-BOOT)") (class "Default")
      (node (ref "C17") (pin "1") (pinfunction "1_1") (pintype "input"))
      (node (ref "U6") (pin "1") (pinfunction "BOOT_1") (pintype "input"))
    )
    (net (code "89") (name "Net-(U6-COMP)") (class "Default")
      (node (ref "R31") (pin "2") (pinfunction "2_2") (pintype "input"))
      (node (ref "U6") (pin "6") (pinfunction "COMP_6") (pintype "input"))
    )
    (net (code "90") (name "Net-(U6-FB)") (class "Default")
      (node (ref "R28") (pin "1") (pinfunction "1_1") (pintype "input"))
      (node (ref "R32") (pin "2") (pinfunction "2_2") (pintype "input"))
      (node (ref "U6") (pin "5") (pinfunction "FB_5") (pintype "input"))
    )
    (net (code "91") (name "Net-(U6-RT{slash}CLK)") (class "Default")
      (node (ref "R29") (pin "2") (pinfunction "2_2") (pintype "input"))
      (node (ref "U6") (pin "4") (pinfunction "RT/CLK_4") (pintype "input"))
    )
    (net (code "92") (name "Net-(U6-SW)") (class "Default")
      (node (ref "C17") (pin "2") (pinfunction "2_2") (pintype "input"))
      (node (ref "L2") (pin "1") (pinfunction "1_1") (pintype "input"))
      (node (ref "U6") (pin "8") (pinfunction "SW_8") (pintype "input"))
    )
    (net (code "93") (name "VCC3V3") (class "Default")
      (node (ref "C7") (pin "1") (pinfunction "1_1") (pintype "input"))
      (node (ref "C8") (pin "2") (pinfunction "2_2") (pintype "input"))
      (node (ref "H1") (pin "2") (pinfunction "2_2") (pintype "input"))
      (node (ref "H15") (pin "1") (pinfunction "1_1") (pintype "unspecified"))
      (node (ref "R1") (pin "1") (pinfunction "1_1") (pintype "input"))
      (node (ref "R12") (pin "1") (pinfunction "1_1") (pintype "input"))
      (node (ref "R8") (pin "2") (pinfunction "2_2") (pintype "input"))
      (node (ref "R9") (pin "2") (pinfunction "2_2") (pintype "input"))
      (node (ref "U3") (pin "5") (pinfunction "VOUT_5") (pintype "input"))
    )
    (net (code "94") (name "VCC5V5") (class "Default")
      (node (ref "C13") (pin "2") (pinfunction "2_2") (pintype "input"))
      (node (ref "C14") (pin "1") (pinfunction "1_1") (pintype "input"))
      (node (ref "C5") (pin "2") (pinfunction "2_2") (pintype "input"))
      (node (ref "C6") (pin "1") (pinfunction "1_1") (pintype "input"))
      (node (ref "D1") (pin "1") (pinfunction "C_1") (pintype "input"))
      (node (ref "H4") (pin "1") (pinfunction "1_1") (pintype "input"))
      (node (ref "H8") (pin "7") (pinfunction "7_7") (pintype "input"))
      (node (ref "R26") (pin "2") (pinfunction "2_2") (pintype "input"))
      (node (ref "R27") (pin "2") (pinfunction "2_2") (pintype "input"))
      (node (ref "U1") (pin "2") (pinfunction "VCC_2") (pintype "input"))
      (node (ref "U3") (pin "1") (pinfunction "VIN_1") (pintype "input"))
      (node (ref "U3") (pin "3") (pinfunction "EN_3") (pintype "input"))
      (node (ref "U5") (pin "1") (pinfunction "VIN_1") (pintype "input"))
      (node (ref "U5") (pin "3") (pinfunction "EN_3") (pintype "input"))
    )
    (net (code "95") (name "VCCBAT") (class "Default")
      (node (ref "C10") (pin "2") (pinfunction "2_2") (pintype "input"))
      (node (ref "C11") (pin "2") (pinfunction "2_2") (pintype "input"))
      (node (ref "C9") (pin "1") (pinfunction "1_1") (pintype "input"))
      (node (ref "CON1") (pin "1") (pinfunction "1_1") (pintype "input"))
      (node (ref "CON2") (pin "1") (pinfunction "1_1") (pintype "input"))
      (node (ref "D2") (pin "2") (pinfunction "A_2") (pintype "input"))
      (node (ref "Q2") (pin "2") (pinfunction "D_2") (pintype "input"))
      (node (ref "U4") (pin "2") (pinfunction "VIN_2") (pintype "input"))
      (node (ref "U4") (pin "3") (pinfunction "EN_3") (pintype "input"))
    )
    (net (code "96") (name "VCCCAM") (class "Default")
      (node (ref "C15") (pin "1") (pinfunction "1_1") (pintype "input"))
      (node (ref "C16") (pin "2") (pinfunction "2_2") (pintype "input"))
      (node (ref "H2") (pin "1") (pinfunction "3V3_1") (pintype "input"))
      (node (ref "R21") (pin "1") (pinfunction "1_1") (pintype "input"))
      (node (ref "U5") (pin "5") (pinfunction "VOUT_5") (pintype "input"))
    )
    (net (code "97") (name "VCCSTEER") (class "Default")
      (node (ref "C2") (pin "2") (pinfunction "2_2") (pintype "input"))
      (node (ref "C3") (pin "1") (pinfunction "1_1") (pintype "input"))
      (node (ref "C4") (pin "2") (pinfunction "2_2") (pintype "input"))
      (node (ref "H10") (pin "2") (pinfunction "2_2") (pintype "input"))
      (node (ref "L1") (pin "2") (pinfunction "2_2") (pintype "input"))
      (node (ref "R10") (pin "2") (pinfunction "2_2") (pintype "input"))
      (node (ref "R11") (pin "2") (pinfunction "2_2") (pintype "input"))
    )
    (net (code "98") (name "unconnected-(H2-HREF-Pad7)") (class "Default")
      (node (ref "H2") (pin "7") (pinfunction "HREF_7") (pintype "input+no_connect"))
    )
    (net (code "99") (name "unconnected-(H5-Pad2)") (class "Default")
      (node (ref "H5") (pin "2") (pinfunction "2_2") (pintype "input+no_connect"))
    )
    (net (code "100") (name "unconnected-(H8-Pad2)") (class "Default")
      (node (ref "H8") (pin "2") (pinfunction "2_2") (pintype "input+no_connect"))
    )
    (net (code "101") (name "unconnected-(H17-Pad2)") (class "Default")
      (node (ref "H17") (pin "2") (pinfunction "2_2") (pintype "input+no_connect"))
    )
    (net (code "102") (name "unconnected-(R8-Pad5)") (class "Default")
      (node (ref "R8") (pin "5") (pinfunction "5_5") (pintype "input+no_connect"))
    )
    (net (code "103") (name "unconnected-(R8-Pad6)") (class "Default")
      (node (ref "R8") (pin "6") (pinfunction "6_6") (pintype "input+no_connect"))
    )
    (net (code "104") (name "unconnected-(R9-Pad5)") (class "Default")
      (node (ref "R9") (pin "5") (pinfunction "5_5") (pintype "input+no_connect"))
    )
    (net (code "105") (name "unconnected-(R9-Pad6)") (class "Default")
      (node (ref "R9") (pin "6") (pinfunction "6_6") (pintype "input+no_connect"))
    )
    (net (code "106") (name "unconnected-(U1-00.8-Pad107)") (class "Default")
      (node (ref "U1") (pin "107") (pinfunction "00.8_107") (pintype "input"))
    )
    (net (code "107") (name "unconnected-(U1-00.9-Pad108)") (class "Default")
      (node (ref "U1") (pin "108") (pinfunction "00.9_108") (pintype "input"))
    )
    (net (code "108") (name "unconnected-(U1-00.12-Pad109)") (class "Default")
      (node (ref "U1") (pin "109") (pinfunction "00.12_109") (pintype "input"))
    )
    (net (code "109") (name "unconnected-(U1-02.4-Pad94)") (class "Default")
      (node (ref "U1") (pin "94") (pinfunction "02.4_94") (pintype "input"))
    )
    (net (code "110") (name "unconnected-(U1-02.5-Pad95)") (class "Default")
      (node (ref "U1") (pin "95") (pinfunction "02.5_95") (pintype "input"))
    )
    (net (code "111") (name "unconnected-(U1-02.8-Pad98)") (class "Default")
      (node (ref "U1") (pin "98") (pinfunction "02.8_98") (pintype "input"))
    )
    (net (code "112") (name "unconnected-(U1-11.9-Pad81)") (class "Default")
      (node (ref "U1") (pin "81") (pinfunction "11.9_81") (pintype "input"))
    )
    (net (code "113") (name "unconnected-(U1-11.10-Pad82)") (class "Default")
      (node (ref "U1") (pin "82") (pinfunction "11.10_82") (pintype "input"))
    )
    (net (code "114") (name "unconnected-(U1-11.11-Pad83)") (class "Default")
      (node (ref "U1") (pin "83") (pinfunction "11.11_83") (pintype "input"))
    )
    (net (code "115") (name "unconnected-(U1-11.12-Pad84)") (class "Default")
      (node (ref "U1") (pin "84") (pinfunction "11.12_84") (pintype "input"))
    )
    (net (code "116") (name "unconnected-(U1-13.0-Pad74)") (class "Default")
      (node (ref "U1") (pin "74") (pinfunction "13.0_74") (pintype "input"))
    )
    (net (code "117") (name "unconnected-(U1-13.1-Pad75)") (class "Default")
      (node (ref "U1") (pin "75") (pinfunction "13.1_75") (pintype "input"))
    )
    (net (code "118") (name "unconnected-(U1-13.2-Pad76)") (class "Default")
      (node (ref "U1") (pin "76") (pinfunction "13.2_76") (pintype "input"))
    )
    (net (code "119") (name "unconnected-(U1-13.3-Pad77)") (class "Default")
      (node (ref "U1") (pin "77") (pinfunction "13.3_77") (pintype "input"))
    )
    (net (code "120") (name "unconnected-(U1-14.0-Pad67)") (class "Default")
      (node (ref "U1") (pin "67") (pinfunction "14.0_67") (pintype "input"))
    )
    (net (code "121") (name "unconnected-(U1-14.1-Pad68)") (class "Default")
      (node (ref "U1") (pin "68") (pinfunction "14.1_68") (pintype "input"))
    )
    (net (code "122") (name "unconnected-(U1-14.2-Pad69)") (class "Default")
      (node (ref "U1") (pin "69") (pinfunction "14.2_69") (pintype "input"))
    )
    (net (code "123") (name "unconnected-(U1-14.3-Pad70)") (class "Default")
      (node (ref "U1") (pin "70") (pinfunction "14.3_70") (pintype "input"))
    )
    (net (code "124") (name "unconnected-(U1-14.4-Pad71)") (class "Default")
      (node (ref "U1") (pin "71") (pinfunction "14.4_71") (pintype "input"))
    )
    (net (code "125") (name "unconnected-(U1-14.5-Pad72)") (class "Default")
      (node (ref "U1") (pin "72") (pinfunction "14.5_72") (pintype "input"))
    )
    (net (code "126") (name "unconnected-(U1-14.6-Pad73)") (class "Default")
      (node (ref "U1") (pin "73") (pinfunction "14.6_73") (pintype "input"))
    )
    (net (code "127") (name "unconnected-(U1-15.8-Pad66)") (class "Default")
      (node (ref "U1") (pin "66") (pinfunction "15.8_66") (pintype "input"))
    )
    (net (code "128") (name "unconnected-(U1-20.0-Pad44)") (class "Default")
      (node (ref "U1") (pin "44") (pinfunction "20.0_44") (pintype "input"))
    )
    (net (code "129") (name "unconnected-(U1-20.2-Pad45)") (class "Default")
      (node (ref "U1") (pin "45") (pinfunction "20.2_45") (pintype "input"))
    )
    (net (code "130") (name "unconnected-(U1-20.3-Pad46)") (class "Default")
      (node (ref "U1") (pin "46") (pinfunction "20.3_46") (pintype "input"))
    )
    (net (code "131") (name "unconnected-(U1-20.9-Pad52)") (class "Default")
      (node (ref "U1") (pin "52") (pinfunction "20.9_52") (pintype "input"))
    )
    (net (code "132") (name "unconnected-(U1-21.6-Pad42)") (class "Default")
      (node (ref "U1") (pin "42") (pinfunction "21.6_42") (pintype "input"))
    )
    (net (code "133") (name "unconnected-(U1-21.7-Pad43)") (class "Default")
      (node (ref "U1") (pin "43") (pinfunction "21.7_43") (pintype "input"))
    )
    (net (code "134") (name "unconnected-(U1-22.0-Pad34)") (class "Default")
      (node (ref "U1") (pin "34") (pinfunction "22.0_34") (pintype "input"))
    )
    (net (code "135") (name "unconnected-(U1-22.1-Pad35)") (class "Default")
      (node (ref "U1") (pin "35") (pinfunction "22.1_35") (pintype "input"))
    )
    (net (code "136") (name "unconnected-(U1-22.2-Pad36)") (class "Default")
      (node (ref "U1") (pin "36") (pinfunction "22.2_36") (pintype "input"))
    )
    (net (code "137") (name "unconnected-(U1-22.3-Pad37)") (class "Default")
      (node (ref "U1") (pin "37") (pinfunction "22.3_37") (pintype "input"))
    )
    (net (code "138") (name "unconnected-(U1-23.1-Pad33)") (class "Default")
      (node (ref "U1") (pin "33") (pinfunction "23.1_33") (pintype "input"))
    )
    (net (code "139") (name "unconnected-(U1-32.4-Pad32)") (class "Default")
      (node (ref "U1") (pin "32") (pinfunction "32.4_32") (pintype "input"))
    )
    (net (code "140") (name "unconnected-(U1-33.8-Pad26)") (class "Default")
      (node (ref "U1") (pin "26") (pinfunction "33.8_26") (pintype "input"))
    )
    (net (code "141") (name "unconnected-(U1-33.11-Pad29)") (class "Default")
      (node (ref "U1") (pin "29") (pinfunction "33.11_29") (pintype "input"))
    )
    (net (code "142") (name "unconnected-(U1-33.12-Pad30)") (class "Default")
      (node (ref "U1") (pin "30") (pinfunction "33.12_30") (pintype "input"))
    )
    (net (code "143") (name "unconnected-(U1-33.13-Pad31)") (class "Default")
      (node (ref "U1") (pin "31") (pinfunction "33.13_31") (pintype "input"))
    )
    (net (code "144") (name "unconnected-(U1-A6-Pad15)") (class "Default")
      (node (ref "U1") (pin "15") (pinfunction "A6_15") (pintype "input"))
    )
    (net (code "145") (name "unconnected-(U1-A7-Pad14)") (class "Default")
      (node (ref "U1") (pin "14") (pinfunction "A7_14") (pintype "input"))
    )
    (net (code "146") (name "unconnected-(U1-A8-Pad13)") (class "Default")
      (node (ref "U1") (pin "13") (pinfunction "A8_13") (pintype "input"))
    )
    (net (code "147") (name "unconnected-(U1-A10-Pad12)") (class "Default")
      (node (ref "U1") (pin "12") (pinfunction "A10_12") (pintype "input"))
    )
    (net (code "148") (name "unconnected-(U1-A11-Pad11)") (class "Default")
      (node (ref "U1") (pin "11") (pinfunction "A11_11") (pintype "input"))
    )
    (net (code "149") (name "unconnected-(U1-A12-Pad10)") (class "Default")
      (node (ref "U1") (pin "10") (pinfunction "A12_10") (pintype "input"))
    )
    (net (code "150") (name "unconnected-(U1-A13-Pad9)") (class "Default")
      (node (ref "U1") (pin "9") (pinfunction "A13_9") (pintype "input"))
    )
    (net (code "151") (name "unconnected-(U1-A16-Pad8)") (class "Default")
      (node (ref "U1") (pin "8") (pinfunction "A16_8") (pintype "input"))
    )
    (net (code "152") (name "unconnected-(U1-A17-Pad7)") (class "Default")
      (node (ref "U1") (pin "7") (pinfunction "A17_7") (pintype "input"))
    )
    (net (code "153") (name "unconnected-(U1-A20-Pad6)") (class "Default")
      (node (ref "U1") (pin "6") (pinfunction "A20_6") (pintype "input"))
    )
    (net (code "154") (name "unconnected-(U1-A21-Pad5)") (class "Default")
      (node (ref "U1") (pin "5") (pinfunction "A21_5") (pintype "input"))
    )
    (net (code "155") (name "unconnected-(U1-A24-Pad122)") (class "Default")
      (node (ref "U1") (pin "122") (pinfunction "A24_122") (pintype "input"))
    )
    (net (code "156") (name "unconnected-(U1-A25-Pad121)") (class "Default")
      (node (ref "U1") (pin "121") (pinfunction "A25_121") (pintype "input"))
    )
    (net (code "157") (name "unconnected-(U1-A35-Pad120)") (class "Default")
      (node (ref "U1") (pin "120") (pinfunction "A35_120") (pintype "input"))
    )
    (net (code "158") (name "unconnected-(U1-A36-Pad119)") (class "Default")
      (node (ref "U1") (pin "119") (pinfunction "A36_119") (pintype "input"))
    )
    (net (code "159") (name "unconnected-(U1-A37-Pad118)") (class "Default")
      (node (ref "U1") (pin "118") (pinfunction "A37_118") (pintype "input"))
    )
    (net (code "160") (name "unconnected-(U1-A38-Pad117)") (class "Default")
      (node (ref "U1") (pin "117") (pinfunction "A38_117") (pintype "input"))
    )
    (net (code "161") (name "unconnected-(U1-A39-Pad116)") (class "Default")
      (node (ref "U1") (pin "116") (pinfunction "A39_116") (pintype "input"))
    )
    (net (code "162") (name "unconnected-(U1-A44-Pad115)") (class "Default")
      (node (ref "U1") (pin "115") (pinfunction "A44_115") (pintype "input"))
    )
    (net (code "163") (name "unconnected-(U1-A45-Pad114)") (class "Default")
      (node (ref "U1") (pin "114") (pinfunction "A45_114") (pintype "input"))
    )
    (net (code "164") (name "unconnected-(U1-A46-Pad113)") (class "Default")
      (node (ref "U1") (pin "113") (pinfunction "A46_113") (pintype "input"))
    )
    (net (code "165") (name "unconnected-(U1-A47-Pad112)") (class "Default")
      (node (ref "U1") (pin "112") (pinfunction "A47_112") (pintype "input"))
    )
    (net (code "166") (name "unconnected-(U1-A48-Pad111)") (class "Default")
      (node (ref "U1") (pin "111") (pinfunction "A48_111") (pintype "input"))
    )
    (net (code "167") (name "unconnected-(U1-A49-Pad110)") (class "Default")
      (node (ref "U1") (pin "110") (pinfunction "A49_110") (pintype "input"))
    )
    (net (code "168") (name "unconnected-(U1-ESR0-Pad48)") (class "Default")
      (node (ref "U1") (pin "48") (pinfunction "ESR0_48") (pintype "input"))
    )
    (net (code "169") (name "unconnected-(U1-ESR1-Pad47)") (class "Default")
      (node (ref "U1") (pin "47") (pinfunction "ESR1_47") (pintype "input"))
    )
    (net (code "170") (name "unconnected-(U1-GND-Pad3)") (class "Default")
      (node (ref "U1") (pin "3") (pinfunction "GND_3") (pintype "input"))
    )
    (net (code "171") (name "unconnected-(U1-VCC-Pad4)") (class "Default")
      (node (ref "U1") (pin "4") (pinfunction "VCC_4") (pintype "input"))
    )
    (net (code "172") (name "unconnected-(U3-NC-Pad4)") (class "Default")
      (node (ref "U3") (pin "4") (pinfunction "NC_4") (pintype "input+no_connect"))
    )
    (net (code "173") (name "unconnected-(U5-NC-Pad4)") (class "Default")
      (node (ref "U5") (pin "4") (pinfunction "NC_4") (pintype "input+no_connect"))
    )
  )
)
